# ledarrows_schematic.net
KiCad netlist of a schematic drawn in EAGLE
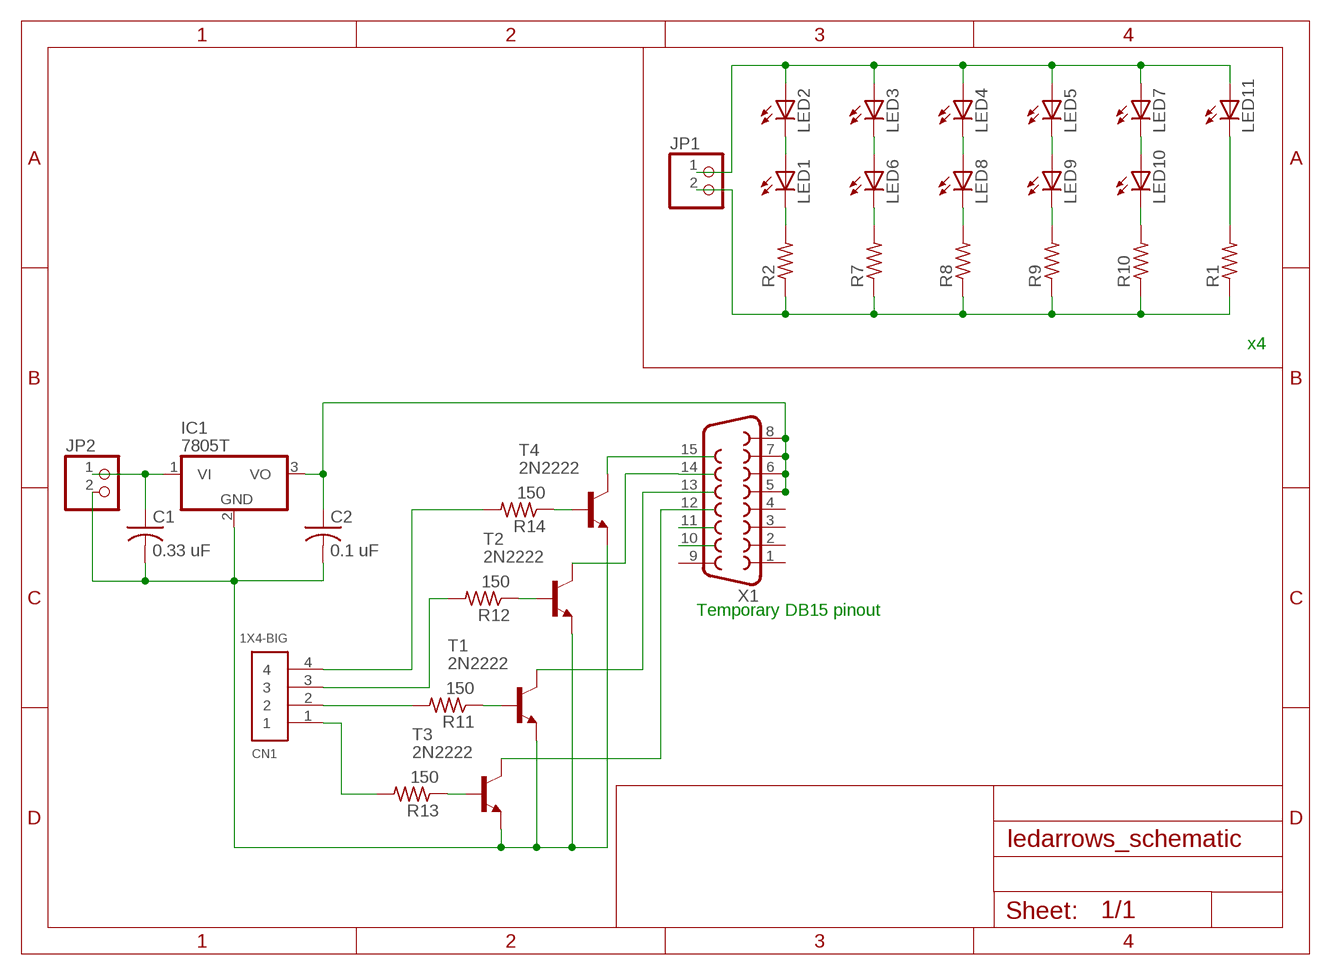
[diagram p0: schematic, sheet 1]

(export (version "E")
  (design (tool "Eeschema 10.0.6"))
  (components
    (comp (ref "C1")
      (value "0.33 uF")
      (footprint "eagle-import:C025-050X050")
      (libsource (lib "eagle-import") (part "C-US025-050X050"))
    )
    (comp (ref "C2")
      (value "0.1 uF")
      (footprint "eagle-import:C025-050X050")
      (libsource (lib "eagle-import") (part "C-US025-050X050"))
    )
    (comp (ref "CN1")
      (value "1X4-BIG")
      (footprint "eagle-import:1X04-BIG")
      (libsource (lib "eagle-import") (part "1X4-BIG"))
    )
    (comp (ref "IC1")
      (value "7805T")
      (footprint "eagle-import:TO220H")
      (libsource (lib "eagle-import") (part "78T05"))
    )
    (comp (ref "JP1")
      (value "PINHD-1X2")
      (footprint "eagle-import:1X02")
      (libsource (lib "eagle-import") (part "PINHD-1X2"))
    )
    (comp (ref "JP2")
      (value "PINHD-1X2")
      (footprint "eagle-import:1X02")
      (libsource (lib "eagle-import") (part "PINHD-1X2"))
    )
    (comp (ref "LED1")
      (value "LED3MM")
      (footprint "eagle-import:LED3MM")
      (libsource (lib "eagle-import") (part "LED3MM"))
    )
    (comp (ref "LED2")
      (value "LED3MM")
      (footprint "eagle-import:LED3MM")
      (libsource (lib "eagle-import") (part "LED3MM"))
    )
    (comp (ref "LED3")
      (value "LED3MM")
      (footprint "eagle-import:LED3MM")
      (libsource (lib "eagle-import") (part "LED3MM"))
    )
    (comp (ref "LED4")
      (value "LED3MM")
      (footprint "eagle-import:LED3MM")
      (libsource (lib "eagle-import") (part "LED3MM"))
    )
    (comp (ref "LED5")
      (value "LED3MM")
      (footprint "eagle-import:LED3MM")
      (libsource (lib "eagle-import") (part "LED3MM"))
    )
    (comp (ref "LED6")
      (value "LED3MM")
      (footprint "eagle-import:LED3MM")
      (libsource (lib "eagle-import") (part "LED3MM"))
    )
    (comp (ref "LED7")
      (value "LED3MM")
      (footprint "eagle-import:LED3MM")
      (libsource (lib "eagle-import") (part "LED3MM"))
    )
    (comp (ref "LED8")
      (value "LED3MM")
      (footprint "eagle-import:LED3MM")
      (libsource (lib "eagle-import") (part "LED3MM"))
    )
    (comp (ref "LED9")
      (value "LED3MM")
      (footprint "eagle-import:LED3MM")
      (libsource (lib "eagle-import") (part "LED3MM"))
    )
    (comp (ref "LED10")
      (value "LED3MM")
      (footprint "eagle-import:LED3MM")
      (libsource (lib "eagle-import") (part "LED3MM"))
    )
    (comp (ref "LED11")
      (value "LED3MM")
      (footprint "eagle-import:LED3MM")
      (libsource (lib "eagle-import") (part "LED3MM"))
    )
    (comp (ref "R1")
      (value "R-US_0204/7")
      (footprint "eagle-import:0204_7")
      (libsource (lib "eagle-import") (part "R-US_0204/7"))
    )
    (comp (ref "R2")
      (value "R-US_0204/7")
      (footprint "eagle-import:0204_7")
      (libsource (lib "eagle-import") (part "R-US_0204/7"))
    )
    (comp (ref "R7")
      (value "R-US_0204/7")
      (footprint "eagle-import:0204_7")
      (libsource (lib "eagle-import") (part "R-US_0204/7"))
    )
    (comp (ref "R8")
      (value "R-US_0204/7")
      (footprint "eagle-import:0204_7")
      (libsource (lib "eagle-import") (part "R-US_0204/7"))
    )
    (comp (ref "R9")
      (value "R-US_0204/7")
      (footprint "eagle-import:0204_7")
      (libsource (lib "eagle-import") (part "R-US_0204/7"))
    )
    (comp (ref "R10")
      (value "R-US_0204/7")
      (footprint "eagle-import:0204_7")
      (libsource (lib "eagle-import") (part "R-US_0204/7"))
    )
    (comp (ref "R11")
      (value "150")
      (footprint "eagle-import:0204_7")
      (libsource (lib "eagle-import") (part "R-US_0204/7"))
    )
    (comp (ref "R12")
      (value "150")
      (footprint "eagle-import:0204_7")
      (libsource (lib "eagle-import") (part "R-US_0204/7"))
    )
    (comp (ref "R13")
      (value "150")
      (footprint "eagle-import:0204_7")
      (libsource (lib "eagle-import") (part "R-US_0204/7"))
    )
    (comp (ref "R14")
      (value "150")
      (footprint "eagle-import:0204_7")
      (libsource (lib "eagle-import") (part "R-US_0204/7"))
    )
    (comp (ref "T1")
      (value "2N2222")
      (footprint "eagle-import:TO92-EBC-OVAL")
      (libsource (lib "eagle-import") (part "2N2222"))
    )
    (comp (ref "T2")
      (value "2N2222")
      (footprint "eagle-import:TO92-EBC-OVAL")
      (libsource (lib "eagle-import") (part "2N2222"))
    )
    (comp (ref "T3")
      (value "2N2222")
      (footprint "eagle-import:TO92-EBC-OVAL")
      (libsource (lib "eagle-import") (part "2N2222"))
    )
    (comp (ref "T4")
      (value "2N2222")
      (footprint "eagle-import:TO92-EBC-OVAL")
      (libsource (lib "eagle-import") (part "2N2222"))
    )
    (comp (ref "X1")
      (value "F15H")
      (footprint "eagle-import:F15H")
      (libsource (lib "eagle-import") (part "F15H"))
    )
  )
  (nets
    (net (code "1") (name "Net-(CN1-Pad1)") (class "Default")
      (node (ref "CN1") (pin "1") (pinfunction "1_1") (pintype "bidirectional"))
      (node (ref "R13") (pin "2") (pinfunction "2_2") (pintype "passive"))
    )
    (net (code "2") (name "Net-(CN1-Pad2)") (class "Default")
      (node (ref "CN1") (pin "2") (pinfunction "2_2") (pintype "bidirectional"))
      (node (ref "R11") (pin "2") (pinfunction "2_2") (pintype "passive"))
    )
    (net (code "3") (name "Net-(CN1-Pad3)") (class "Default")
      (node (ref "CN1") (pin "3") (pinfunction "3_3") (pintype "bidirectional"))
      (node (ref "R12") (pin "2") (pinfunction "2_2") (pintype "passive"))
    )
    (net (code "4") (name "Net-(CN1-Pad4)") (class "Default")
      (node (ref "CN1") (pin "4") (pinfunction "4_4") (pintype "bidirectional"))
      (node (ref "R14") (pin "2") (pinfunction "2_2") (pintype "passive"))
    )
    (net (code "5") (name "Net-(IC1-GND)") (class "Default")
      (node (ref "C1") (pin "2") (pinfunction "2_2") (pintype "passive"))
      (node (ref "C2") (pin "2") (pinfunction "2_2") (pintype "passive"))
      (node (ref "IC1") (pin "2") (pinfunction "GND_2") (pintype "passive"))
      (node (ref "JP2") (pin "2") (pinfunction "2_2") (pintype "passive"))
      (node (ref "T1") (pin "E") (pinfunction "E_E") (pintype "passive"))
      (node (ref "T2") (pin "E") (pinfunction "E_E") (pintype "passive"))
      (node (ref "T3") (pin "E") (pinfunction "E_E") (pintype "passive"))
      (node (ref "T4") (pin "E") (pinfunction "E_E") (pintype "passive"))
    )
    (net (code "6") (name "Net-(IC1-VI)") (class "Default")
      (node (ref "C1") (pin "1") (pinfunction "1_1") (pintype "passive"))
      (node (ref "IC1") (pin "1") (pinfunction "VI_1") (pintype "input"))
      (node (ref "JP2") (pin "1") (pinfunction "1_1") (pintype "passive"))
    )
    (net (code "7") (name "Net-(IC1-VO)") (class "Default")
      (node (ref "C2") (pin "1") (pinfunction "1_1") (pintype "passive"))
      (node (ref "IC1") (pin "3") (pinfunction "VO_3") (pintype "passive"))
      (node (ref "X1") (pin "5") (pinfunction "5_5") (pintype "passive"))
      (node (ref "X1") (pin "6") (pinfunction "6_6") (pintype "passive"))
      (node (ref "X1") (pin "7") (pinfunction "7_7") (pintype "passive"))
      (node (ref "X1") (pin "8") (pinfunction "8_8") (pintype "passive"))
    )
    (net (code "8") (name "Net-(JP1-Pad1)") (class "Default")
      (node (ref "JP1") (pin "1") (pinfunction "1_1") (pintype "passive"))
      (node (ref "LED11") (pin "A") (pinfunction "A_A") (pintype "passive"))
      (node (ref "LED2") (pin "A") (pinfunction "A_A") (pintype "passive"))
      (node (ref "LED3") (pin "A") (pinfunction "A_A") (pintype "passive"))
      (node (ref "LED4") (pin "A") (pinfunction "A_A") (pintype "passive"))
      (node (ref "LED5") (pin "A") (pinfunction "A_A") (pintype "passive"))
      (node (ref "LED7") (pin "A") (pinfunction "A_A") (pintype "passive"))
    )
    (net (code "9") (name "Net-(JP1-Pad2)") (class "Default")
      (node (ref "JP1") (pin "2") (pinfunction "2_2") (pintype "passive"))
      (node (ref "R1") (pin "1") (pinfunction "1_1") (pintype "passive"))
      (node (ref "R10") (pin "1") (pinfunction "1_1") (pintype "passive"))
      (node (ref "R2") (pin "1") (pinfunction "1_1") (pintype "passive"))
      (node (ref "R7") (pin "1") (pinfunction "1_1") (pintype "passive"))
      (node (ref "R8") (pin "1") (pinfunction "1_1") (pintype "passive"))
      (node (ref "R9") (pin "1") (pinfunction "1_1") (pintype "passive"))
    )
    (net (code "10") (name "Net-(LED1-C)") (class "Default")
      (node (ref "LED1") (pin "K") (pinfunction "C_K") (pintype "passive"))
      (node (ref "R2") (pin "2") (pinfunction "2_2") (pintype "passive"))
    )
    (net (code "11") (name "Net-(LED2-C)") (class "Default")
      (node (ref "LED1") (pin "A") (pinfunction "A_A") (pintype "passive"))
      (node (ref "LED2") (pin "K") (pinfunction "C_K") (pintype "passive"))
    )
    (net (code "12") (name "Net-(LED3-C)") (class "Default")
      (node (ref "LED3") (pin "K") (pinfunction "C_K") (pintype "passive"))
      (node (ref "LED6") (pin "A") (pinfunction "A_A") (pintype "passive"))
    )
    (net (code "13") (name "Net-(LED4-C)") (class "Default")
      (node (ref "LED4") (pin "K") (pinfunction "C_K") (pintype "passive"))
      (node (ref "LED8") (pin "A") (pinfunction "A_A") (pintype "passive"))
    )
    (net (code "14") (name "Net-(LED5-C)") (class "Default")
      (node (ref "LED5") (pin "K") (pinfunction "C_K") (pintype "passive"))
      (node (ref "LED9") (pin "A") (pinfunction "A_A") (pintype "passive"))
    )
    (net (code "15") (name "Net-(LED6-C)") (class "Default")
      (node (ref "LED6") (pin "K") (pinfunction "C_K") (pintype "passive"))
      (node (ref "R7") (pin "2") (pinfunction "2_2") (pintype "passive"))
    )
    (net (code "16") (name "Net-(LED7-C)") (class "Default")
      (node (ref "LED10") (pin "A") (pinfunction "A_A") (pintype "passive"))
      (node (ref "LED7") (pin "K") (pinfunction "C_K") (pintype "passive"))
    )
    (net (code "17") (name "Net-(LED8-C)") (class "Default")
      (node (ref "LED8") (pin "K") (pinfunction "C_K") (pintype "passive"))
      (node (ref "R8") (pin "2") (pinfunction "2_2") (pintype "passive"))
    )
    (net (code "18") (name "Net-(LED9-C)") (class "Default")
      (node (ref "LED9") (pin "K") (pinfunction "C_K") (pintype "passive"))
      (node (ref "R9") (pin "2") (pinfunction "2_2") (pintype "passive"))
    )
    (net (code "19") (name "Net-(LED10-C)") (class "Default")
      (node (ref "LED10") (pin "K") (pinfunction "C_K") (pintype "passive"))
      (node (ref "R10") (pin "2") (pinfunction "2_2") (pintype "passive"))
    )
    (net (code "20") (name "Net-(LED11-C)") (class "Default")
      (node (ref "LED11") (pin "K") (pinfunction "C_K") (pintype "passive"))
      (node (ref "R1") (pin "2") (pinfunction "2_2") (pintype "passive"))
    )
    (net (code "21") (name "Net-(R11-Pad1)") (class "Default")
      (node (ref "R11") (pin "1") (pinfunction "1_1") (pintype "passive"))
      (node (ref "T1") (pin "B") (pinfunction "B_B") (pintype "passive"))
    )
    (net (code "22") (name "Net-(R12-Pad1)") (class "Default")
      (node (ref "R12") (pin "1") (pinfunction "1_1") (pintype "passive"))
      (node (ref "T2") (pin "B") (pinfunction "B_B") (pintype "passive"))
    )
    (net (code "23") (name "Net-(R13-Pad1)") (class "Default")
      (node (ref "R13") (pin "1") (pinfunction "1_1") (pintype "passive"))
      (node (ref "T3") (pin "B") (pinfunction "B_B") (pintype "passive"))
    )
    (net (code "24") (name "Net-(R14-Pad1)") (class "Default")
      (node (ref "R14") (pin "1") (pinfunction "1_1") (pintype "passive"))
      (node (ref "T4") (pin "B") (pinfunction "B_B") (pintype "passive"))
    )
    (net (code "25") (name "Net-(T1-PadC)") (class "Default")
      (node (ref "T1") (pin "C") (pinfunction "C_C") (pintype "passive"))
      (node (ref "X1") (pin "13") (pinfunction "13_13") (pintype "passive"))
    )
    (net (code "26") (name "Net-(T2-PadC)") (class "Default")
      (node (ref "T2") (pin "C") (pinfunction "C_C") (pintype "passive"))
      (node (ref "X1") (pin "14") (pinfunction "14_14") (pintype "passive"))
    )
    (net (code "27") (name "Net-(T3-PadC)") (class "Default")
      (node (ref "T3") (pin "C") (pinfunction "C_C") (pintype "passive"))
      (node (ref "X1") (pin "12") (pinfunction "12_12") (pintype "passive"))
    )
    (net (code "28") (name "Net-(T4-PadC)") (class "Default")
      (node (ref "T4") (pin "C") (pinfunction "C_C") (pintype "passive"))
      (node (ref "X1") (pin "15") (pinfunction "15_15") (pintype "passive"))
    )
    (net (code "29") (name "unconnected-(X1-Pad1)") (class "Default")
      (node (ref "X1") (pin "1") (pinfunction "1_1") (pintype "passive"))
    )
    (net (code "30") (name "unconnected-(X1-Pad2)") (class "Default")
      (node (ref "X1") (pin "2") (pinfunction "2_2") (pintype "passive"))
    )
    (net (code "31") (name "unconnected-(X1-Pad3)") (class "Default")
      (node (ref "X1") (pin "3") (pinfunction "3_3") (pintype "passive"))
    )
    (net (code "32") (name "unconnected-(X1-Pad4)") (class "Default")
      (node (ref "X1") (pin "4") (pinfunction "4_4") (pintype "passive"))
    )
    (net (code "33") (name "unconnected-(X1-Pad9)") (class "Default")
      (node (ref "X1") (pin "9") (pinfunction "9_9") (pintype "passive"))
    )
    (net (code "34") (name "unconnected-(X1-Pad10)") (class "Default")
      (node (ref "X1") (pin "10") (pinfunction "10_10") (pintype "passive"))
    )
    (net (code "35") (name "unconnected-(X1-Pad11)") (class "Default")
      (node (ref "X1") (pin "11") (pinfunction "11_11") (pintype "passive"))
    )
  )
)
